# AMX_sensors30.net
KiCad netlist of a schematic drawn in Altium Designer
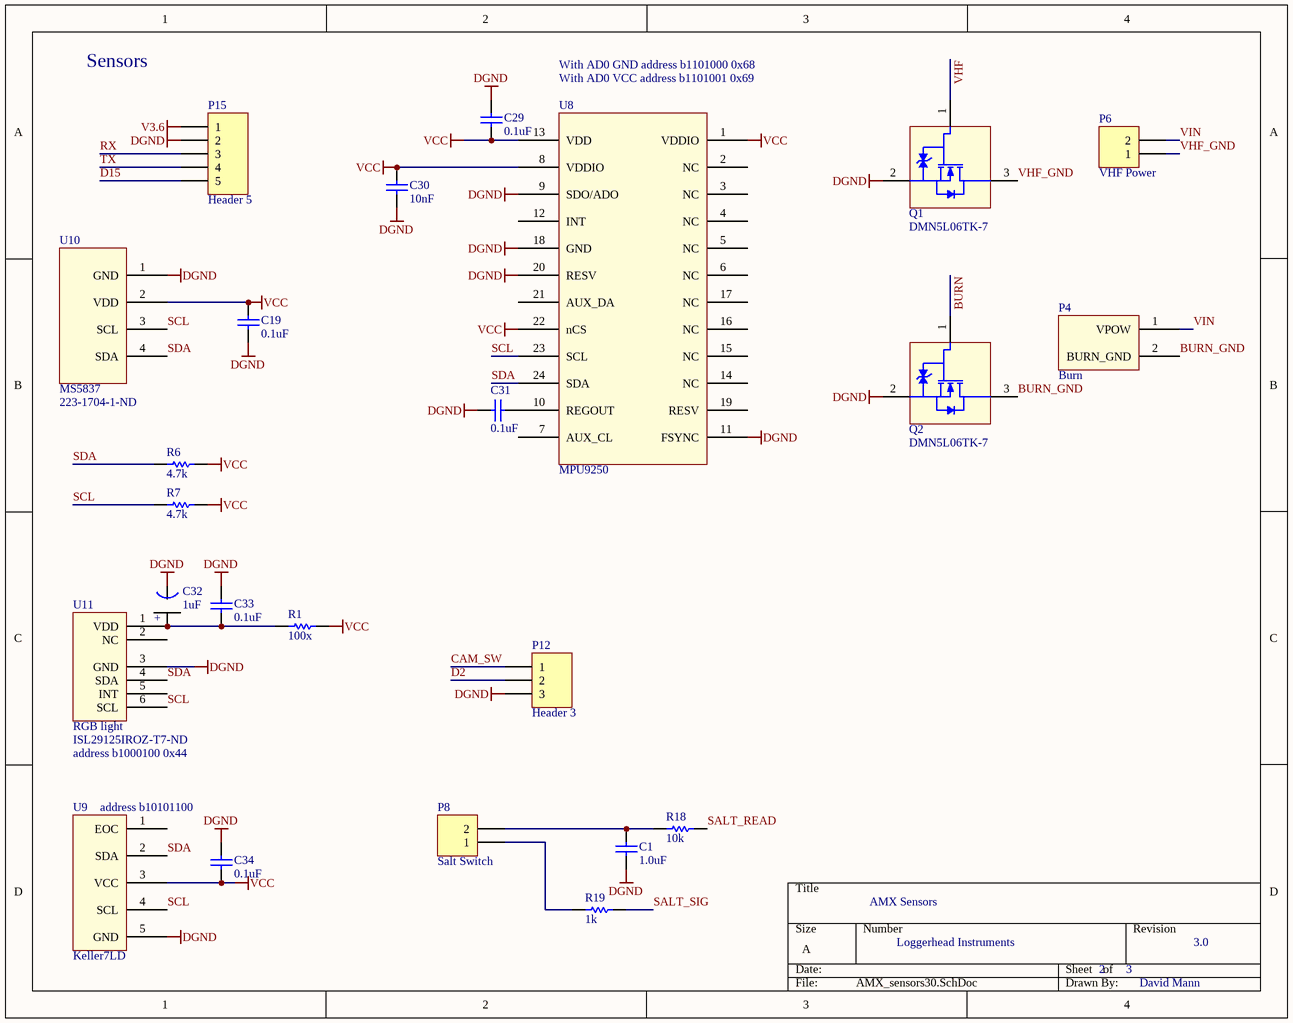
[diagram p0: AMX_sensors30.SchDoc]

(export (version "E")
  (design (tool "Eeschema 10.0.6"))
  (components
    (comp (ref "C1")
      (value "1.0uF")
      (footprint "0402")
      (description "Ceramic Chip Capacitor - Standard")
      (fields (field (name "PUBLISHER") "Altium Limited"))
      (libsource (lib "KEMET Chip Capacitor") (part "C0402"))
    )
    (comp (ref "C19")
      (value "0.1uF")
      (footprint "0402")
      (description "Ceramic Chip Capacitor - Standard")
      (fields (field (name "PUBLISHER") "Altium Limited"))
      (libsource (lib "KEMET Chip Capacitor") (part "C0402"))
    )
    (comp (ref "C29")
      (value "0.1uF")
      (footprint "0402")
      (description "Ceramic Chip Capacitor - Standard")
      (fields (field (name "PUBLISHER") "Altium Limited"))
      (libsource (lib "KEMET Chip Capacitor") (part "C0402"))
    )
    (comp (ref "C30")
      (value "10nF")
      (footprint "0402")
      (description "Ceramic Chip Capacitor - Standard")
      (fields (field (name "PUBLISHER") "Altium Limited"))
      (libsource (lib "KEMET Chip Capacitor") (part "C0402"))
    )
    (comp (ref "C31")
      (value "0.1uF")
      (footprint "0402")
      (description "Ceramic Chip Capacitor - Standard")
      (fields (field (name "PUBLISHER") "Altium Limited"))
      (libsource (lib "KEMET Chip Capacitor") (part "C0402"))
    )
    (comp (ref "C32") (value "1uF") (footprint "Tant0805") (libsource (lib "Loggerhead") (part "Tant0805")))
    (comp (ref "C33")
      (value "0.1uF")
      (footprint "0402")
      (description "Ceramic Chip Capacitor - Standard")
      (fields (field (name "PUBLISHER") "Altium Limited"))
      (libsource (lib "KEMET Chip Capacitor") (part "C0402"))
    )
    (comp (ref "C34")
      (value "0.1uF")
      (footprint "0402")
      (description "Ceramic Chip Capacitor - Standard")
      (fields (field (name "PUBLISHER") "Altium Limited"))
      (libsource (lib "KEMET Chip Capacitor") (part "C0402"))
    )
    (comp (ref "P4") (value "Burn") (footprint "BURN") (libsource (lib "Loggerhead") (part "Burn Screw")))
    (comp (ref "P6")
      (value "VHF Power")
      (footprint "HDR1X2")
      (description "Header, 2-Pin")
      (fields (field (name "PUBLISHER") "Altium Limited"))
      (libsource (lib "Miscellaneous Connectors") (part "Header 2"))
    )
    (comp (ref "P8")
      (value "Salt Switch")
      (footprint "HDR1X2")
      (description "Header, 2-Pin")
      (fields (field (name "PUBLISHER") "Altium Limited"))
      (libsource (lib "Miscellaneous Connectors") (part "Header 2"))
    )
    (comp (ref "P12")
      (value "Header 3")
      (footprint "HDR1X3")
      (description "Header, 3-Pin")
      (fields (field (name "PUBLISHER") "Altium Limited"))
      (libsource (lib "Miscellaneous Connectors") (part "Header 3"))
    )
    (comp (ref "P15")
      (value "Header 5")
      (footprint "HDR1X5")
      (description "Header, 5-Pin")
      (fields (field (name "PUBLISHER") "Altium Limited"))
      (libsource (lib "Miscellaneous Connectors") (part "Header 5"))
    )
    (comp (ref "Q1")
      (value "DMN5L06TK-7")
      (footprint "SOT-523")
      (description "Ultra-low leakage Enhanced MOSFET")
      (fields
        (field (name "CREATOR AND DATE") "Will Flanery 2010-09-02")
        (field (name "FOOTPRINT VERIFIED BY") "*")
        (field (name "SCHEMATIC VERIFIED BY") "*")
        (field (name "VENDOR INFO VERIFIED BY") "*")
      )
      (libsource (lib "Flanery") (part "FET DMN5L06TK-7"))
    )
    (comp (ref "Q2")
      (value "DMN5L06TK-7")
      (footprint "SOT-523")
      (description "Ultra-low leakage Enhanced MOSFET")
      (fields
        (field (name "CREATOR AND DATE") "Will Flanery 2010-09-02")
        (field (name "FOOTPRINT VERIFIED BY") "*")
        (field (name "SCHEMATIC VERIFIED BY") "*")
        (field (name "VENDOR INFO VERIFIED BY") "*")
      )
      (libsource (lib "Flanery") (part "FET DMN5L06TK-7"))
    )
    (comp (ref "R1")
      (value "100x")
      (footprint "3-0603")
      (fields (field (name "PUBLISHER") "Altium Limited"))
      (libsource (lib "Panasonic Resistor") (part "ERJ3RK"))
    )
    (comp (ref "R6")
      (value "4.7k")
      (footprint "3-0603")
      (fields (field (name "PUBLISHER") "Altium Limited"))
      (libsource (lib "Panasonic Resistor") (part "ERJ3RK"))
    )
    (comp (ref "R7")
      (value "4.7k")
      (footprint "3-0603")
      (fields (field (name "PUBLISHER") "Altium Limited"))
      (libsource (lib "Panasonic Resistor") (part "ERJ3RK"))
    )
    (comp (ref "R18")
      (value "10k")
      (footprint "3-0603")
      (fields (field (name "PUBLISHER") "Altium Limited"))
      (libsource (lib "Panasonic Resistor") (part "ERJ3RK"))
    )
    (comp (ref "R19")
      (value "1k")
      (footprint "3-0603")
      (fields (field (name "PUBLISHER") "Altium Limited"))
      (libsource (lib "Panasonic Resistor") (part "ERJ3RK"))
    )
    (comp (ref "U8")
      (value "MPU9250")
      (footprint "MPU6500")
      (description "Invensense")
      (libsource (lib "Loggerhead") (part "MPU-9250"))
    )
    (comp (ref "U9")
      (value "Keller7LD")
      (footprint "Keller7LD")
      (description "Keller Pressure/Temp")
      (libsource (lib "Loggerhead") (part "Keller 7LD"))
    )
    (comp (ref "U10")
      (value "MS5837")
      (footprint "MS5837")
      (description "Pressure/Temp")
      (fields (field (name "SUPPLIER PART NUMBER 1") "223-1704-1-ND"))
      (libsource (lib "Loggerhead") (part "MS5837"))
    )
    (comp (ref "U11")
      (value "RGB light")
      (footprint "ODFN")
      (description "RGB light sensor")
      (fields (field (name "SUPPLIER PART NUMBER 1") "ISL29125IROZ-T7-ND"))
      (libsource (lib "Loggerhead") (part "ISL29125"))
    )
  )
  (nets
    (net (code "1") (name "/BURN") (class "Default")
      (node (ref "Q2") (pin "1") (pinfunction "G_1") (pintype "passive"))
    )
    (net (code "2") (name "/BURN_GND") (class "Default")
      (node (ref "P4") (pin "2") (pinfunction "BURN_GND_2") (pintype "passive"))
      (node (ref "Q2") (pin "3") (pinfunction "D_3") (pintype "passive"))
    )
    (net (code "3") (name "/CAM_SW") (class "Default")
      (node (ref "P12") (pin "1") (pinfunction "1_1") (pintype "passive"))
    )
    (net (code "4") (name "/D2") (class "Default")
      (node (ref "P12") (pin "2") (pinfunction "2_2") (pintype "passive"))
    )
    (net (code "5") (name "/D15") (class "Default")
      (node (ref "P15") (pin "5") (pinfunction "5_5") (pintype "passive"))
    )
    (net (code "6") (name "/RX") (class "Default")
      (node (ref "P15") (pin "3") (pinfunction "3_3") (pintype "passive"))
    )
    (net (code "7") (name "/SALT_READ") (class "Default")
      (node (ref "R18") (pin "1") (pinfunction "1_1") (pintype "passive"))
    )
    (net (code "8") (name "/SALT_SIG") (class "Default")
      (node (ref "R19") (pin "2") (pinfunction "2_2") (pintype "passive"))
    )
    (net (code "9") (name "/SCL") (class "Default")
      (node (ref "R7") (pin "1") (pinfunction "1_1") (pintype "passive"))
      (node (ref "U10") (pin "3") (pinfunction "SCL_3") (pintype "passive"))
      (node (ref "U11") (pin "6") (pinfunction "SCL_6") (pintype "passive"))
      (node (ref "U8") (pin "23") (pinfunction "SCL_23") (pintype "passive"))
      (node (ref "U9") (pin "4") (pinfunction "SCL_4") (pintype "passive"))
    )
    (net (code "10") (name "/SDA") (class "Default")
      (node (ref "R6") (pin "2") (pinfunction "2_2") (pintype "passive"))
      (node (ref "U10") (pin "4") (pinfunction "SDA_4") (pintype "passive"))
      (node (ref "U11") (pin "4") (pinfunction "SDA_4") (pintype "passive"))
      (node (ref "U8") (pin "24") (pinfunction "SDA_24") (pintype "passive"))
      (node (ref "U9") (pin "2") (pinfunction "SDA_2") (pintype "passive"))
    )
    (net (code "11") (name "/TX") (class "Default")
      (node (ref "P15") (pin "4") (pinfunction "4_4") (pintype "passive"))
    )
    (net (code "12") (name "/VHF") (class "Default")
      (node (ref "Q1") (pin "1") (pinfunction "G_1") (pintype "passive"))
    )
    (net (code "13") (name "/VHF_GND") (class "Default")
      (node (ref "P6") (pin "1") (pinfunction "1_1") (pintype "passive"))
      (node (ref "Q1") (pin "3") (pinfunction "D_3") (pintype "passive"))
    )
    (net (code "14") (name "/VIN") (class "Default")
      (node (ref "P4") (pin "1") (pinfunction "VPOW_1") (pintype "passive"))
      (node (ref "P6") (pin "2") (pinfunction "2_2") (pintype "passive"))
    )
    (net (code "15") (name "DGND") (class "Default")
      (node (ref "C1") (pin "2") (pinfunction "2_2") (pintype "passive"))
      (node (ref "C19") (pin "1") (pinfunction "1_1") (pintype "passive"))
      (node (ref "C29") (pin "2") (pinfunction "2_2") (pintype "passive"))
      (node (ref "C30") (pin "2") (pinfunction "2_2") (pintype "passive"))
      (node (ref "C31") (pin "1") (pinfunction "1_1") (pintype "passive"))
      (node (ref "C32") (pin "1") (pinfunction "GND_1") (pintype "passive"))
      (node (ref "C33") (pin "2") (pinfunction "2_2") (pintype "passive"))
      (node (ref "C34") (pin "2") (pinfunction "2_2") (pintype "passive"))
      (node (ref "P12") (pin "3") (pinfunction "3_3") (pintype "passive"))
      (node (ref "P15") (pin "2") (pinfunction "2_2") (pintype "passive"))
      (node (ref "Q1") (pin "2") (pinfunction "S_2") (pintype "passive"))
      (node (ref "Q2") (pin "2") (pinfunction "S_2") (pintype "passive"))
      (node (ref "U10") (pin "1") (pinfunction "GND_1") (pintype "passive"))
      (node (ref "U11") (pin "3") (pinfunction "GND_3") (pintype "passive"))
      (node (ref "U8") (pin "11") (pinfunction "FSYNC_11") (pintype "passive"))
      (node (ref "U8") (pin "18") (pinfunction "GND_18") (pintype "passive"))
      (node (ref "U8") (pin "20") (pinfunction "RESV_20") (pintype "passive"))
      (node (ref "U8") (pin "9") (pinfunction "SDO/ADO_9") (pintype "passive"))
      (node (ref "U9") (pin "5") (pinfunction "GND_5") (pintype "passive"))
    )
    (net (code "16") (name "Net-(C1-Pad1)") (class "Default")
      (node (ref "C1") (pin "1") (pinfunction "1_1") (pintype "passive"))
      (node (ref "P8") (pin "2") (pinfunction "2_2") (pintype "passive"))
      (node (ref "R18") (pin "2") (pinfunction "2_2") (pintype "passive"))
    )
    (net (code "17") (name "Net-(C32-+)") (class "Default")
      (node (ref "C32") (pin "2") (pinfunction "+_2") (pintype "passive"))
      (node (ref "C33") (pin "1") (pinfunction "1_1") (pintype "passive"))
      (node (ref "R1") (pin "2") (pinfunction "2_2") (pintype "passive"))
      (node (ref "U11") (pin "1") (pinfunction "VDD_1") (pintype "passive"))
    )
    (net (code "18") (name "Net-(P8-Pad1)") (class "Default")
      (node (ref "P8") (pin "1") (pinfunction "1_1") (pintype "passive"))
      (node (ref "R19") (pin "1") (pinfunction "1_1") (pintype "passive"))
    )
    (net (code "19") (name "Net-(U8-REGOUT)") (class "Default")
      (node (ref "C31") (pin "2") (pinfunction "2_2") (pintype "passive"))
      (node (ref "U8") (pin "10") (pinfunction "REGOUT_10") (pintype "passive"))
    )
    (net (code "20") (name "V3.6") (class "Default")
      (node (ref "P15") (pin "1") (pinfunction "1_1") (pintype "passive"))
    )
    (net (code "21") (name "VCC") (class "Default")
      (node (ref "C19") (pin "2") (pinfunction "2_2") (pintype "passive"))
      (node (ref "C29") (pin "1") (pinfunction "1_1") (pintype "passive"))
      (node (ref "C30") (pin "1") (pinfunction "1_1") (pintype "passive"))
      (node (ref "C34") (pin "1") (pinfunction "1_1") (pintype "passive"))
      (node (ref "R1") (pin "1") (pinfunction "1_1") (pintype "passive"))
      (node (ref "R6") (pin "1") (pinfunction "1_1") (pintype "passive"))
      (node (ref "R7") (pin "2") (pinfunction "2_2") (pintype "passive"))
      (node (ref "U10") (pin "2") (pinfunction "VDD_2") (pintype "passive"))
      (node (ref "U8") (pin "1") (pinfunction "VDDIO_1") (pintype "passive"))
      (node (ref "U8") (pin "13") (pinfunction "VDD_13") (pintype "passive"))
      (node (ref "U8") (pin "22") (pinfunction "nCS_22") (pintype "passive"))
      (node (ref "U8") (pin "8") (pinfunction "VDDIO_8") (pintype "passive"))
      (node (ref "U9") (pin "3") (pinfunction "VCC_3") (pintype "passive"))
    )
    (net (code "22") (name "unconnected-(U8-AUX_CL-Pad7)") (class "Default")
      (node (ref "U8") (pin "7") (pinfunction "AUX_CL_7") (pintype "passive"))
    )
    (net (code "23") (name "unconnected-(U8-AUX_DA-Pad21)") (class "Default")
      (node (ref "U8") (pin "21") (pinfunction "AUX_DA_21") (pintype "passive"))
    )
    (net (code "24") (name "unconnected-(U8-INT-Pad12)") (class "Default")
      (node (ref "U8") (pin "12") (pinfunction "INT_12") (pintype "passive"))
    )
    (net (code "25") (name "unconnected-(U8-NC-Pad2)") (class "Default")
      (node (ref "U8") (pin "2") (pinfunction "NC_2") (pintype "passive"))
    )
    (net (code "26") (name "unconnected-(U8-NC-Pad3)") (class "Default")
      (node (ref "U8") (pin "3") (pinfunction "NC_3") (pintype "passive"))
    )
    (net (code "27") (name "unconnected-(U8-NC-Pad4)") (class "Default")
      (node (ref "U8") (pin "4") (pinfunction "NC_4") (pintype "passive"))
    )
    (net (code "28") (name "unconnected-(U8-NC-Pad5)") (class "Default")
      (node (ref "U8") (pin "5") (pinfunction "NC_5") (pintype "passive"))
    )
    (net (code "29") (name "unconnected-(U8-NC-Pad6)") (class "Default")
      (node (ref "U8") (pin "6") (pinfunction "NC_6") (pintype "passive"))
    )
    (net (code "30") (name "unconnected-(U8-NC-Pad14)") (class "Default")
      (node (ref "U8") (pin "14") (pinfunction "NC_14") (pintype "passive"))
    )
    (net (code "31") (name "unconnected-(U8-NC-Pad15)") (class "Default")
      (node (ref "U8") (pin "15") (pinfunction "NC_15") (pintype "passive"))
    )
    (net (code "32") (name "unconnected-(U8-NC-Pad16)") (class "Default")
      (node (ref "U8") (pin "16") (pinfunction "NC_16") (pintype "passive"))
    )
    (net (code "33") (name "unconnected-(U8-NC-Pad17)") (class "Default")
      (node (ref "U8") (pin "17") (pinfunction "NC_17") (pintype "passive"))
    )
    (net (code "34") (name "unconnected-(U8-RESV-Pad19)") (class "Default")
      (node (ref "U8") (pin "19") (pinfunction "RESV_19") (pintype "passive"))
    )
    (net (code "35") (name "unconnected-(U9-EOC-Pad1)") (class "Default")
      (node (ref "U9") (pin "1") (pinfunction "EOC_1") (pintype "passive"))
    )
    (net (code "36") (name "unconnected-(U11-INT-Pad5)") (class "Default")
      (node (ref "U11") (pin "5") (pinfunction "INT_5") (pintype "passive"))
    )
    (net (code "37") (name "unconnected-(U11-NC-Pad2)") (class "Default")
      (node (ref "U11") (pin "2") (pinfunction "NC_2") (pintype "passive"))
    )
  )
)
